# Quasar_Control_Board_v0_1.net
KiCad netlist of a schematic drawn in EAGLE
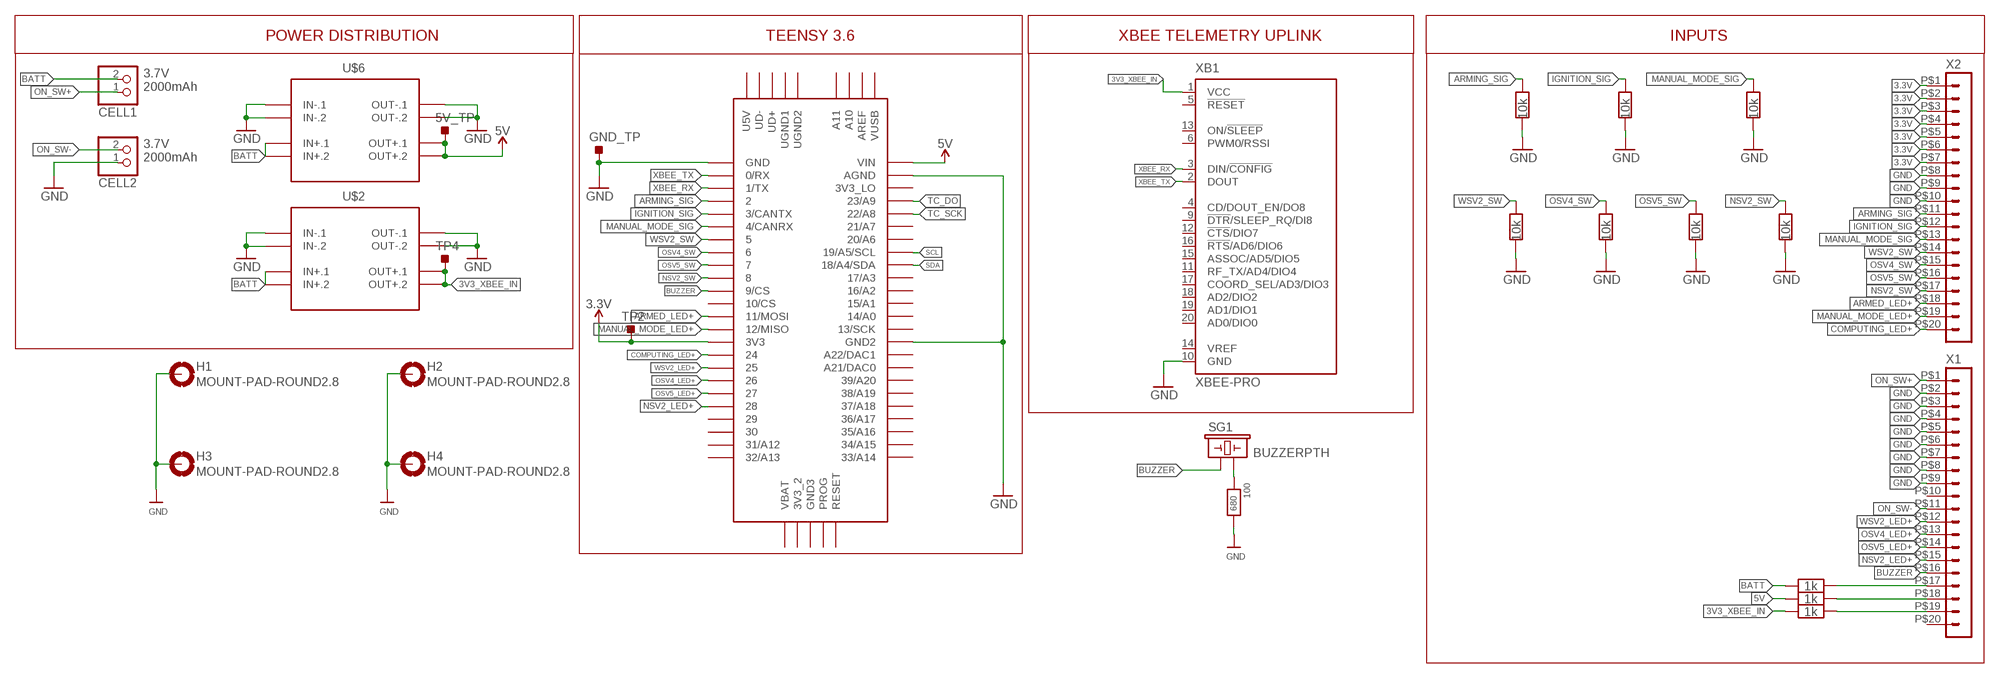
[diagram p0: schematic, sheet 1]

(export (version "E")
  (design (tool "Eeschema 10.0.6"))
  (components
    (comp (ref "5V_TP")
      (value "TESTPOINT_TPS-SMD-10SN")
      (footprint "eagle-import:TESTPOINT_SMD-10SN")
      (libsource (lib "eagle-import") (part "TESTPOINT_TPS-SMD-10SN"))
    )
    (comp (ref "100")
      (value "680")
      (footprint "eagle-import:0603")
      (libsource (lib "eagle-import") (part "RESISTOR0603"))
    )
    (comp (ref "CELL1")
      (value "JSTPH")
      (footprint "eagle-import:JSTPH2")
      (libsource (lib "eagle-import") (part "JST_2PIN"))
    )
    (comp (ref "CELL2")
      (value "JSTPH")
      (footprint "eagle-import:JSTPH2")
      (libsource (lib "eagle-import") (part "JST_2PIN"))
    )
    (comp (ref "GND_TP")
      (value "TESTPOINT_TPS-SMD-10SN")
      (footprint "eagle-import:TESTPOINT_SMD-10SN")
      (libsource (lib "eagle-import") (part "TESTPOINT_TPS-SMD-10SN"))
    )
    (comp (ref "H1")
      (value "MOUNT-PAD-ROUND2.8")
      (footprint "eagle-import:2,8-PAD")
      (libsource (lib "eagle-import") (part "MOUNT-PAD-ROUND2.8"))
    )
    (comp (ref "H2")
      (value "MOUNT-PAD-ROUND2.8")
      (footprint "eagle-import:2,8-PAD")
      (libsource (lib "eagle-import") (part "MOUNT-PAD-ROUND2.8"))
    )
    (comp (ref "H3")
      (value "MOUNT-PAD-ROUND2.8")
      (footprint "eagle-import:2,8-PAD")
      (libsource (lib "eagle-import") (part "MOUNT-PAD-ROUND2.8"))
    )
    (comp (ref "H4")
      (value "MOUNT-PAD-ROUND2.8")
      (footprint "eagle-import:2,8-PAD")
      (libsource (lib "eagle-import") (part "MOUNT-PAD-ROUND2.8"))
    )
    (comp (ref "R1")
      (value "10k")
      (footprint "eagle-import:0805")
      (libsource (lib "eagle-import") (part "RESISTOR0805"))
    )
    (comp (ref "R2")
      (value "10k")
      (footprint "eagle-import:0805")
      (libsource (lib "eagle-import") (part "RESISTOR0805"))
    )
    (comp (ref "R3")
      (value "10k")
      (footprint "eagle-import:0805")
      (libsource (lib "eagle-import") (part "RESISTOR0805"))
    )
    (comp (ref "R4")
      (value "10k")
      (footprint "eagle-import:0805")
      (libsource (lib "eagle-import") (part "RESISTOR0805"))
    )
    (comp (ref "R5")
      (value "10k")
      (footprint "eagle-import:0805")
      (libsource (lib "eagle-import") (part "RESISTOR0805"))
    )
    (comp (ref "R6")
      (value "10k")
      (footprint "eagle-import:0805")
      (libsource (lib "eagle-import") (part "RESISTOR0805"))
    )
    (comp (ref "R7")
      (value "10k")
      (footprint "eagle-import:0805")
      (libsource (lib "eagle-import") (part "RESISTOR0805"))
    )
    (comp (ref "R8")
      (value "1k")
      (footprint "eagle-import:0805")
      (libsource (lib "eagle-import") (part "RESISTOR0805"))
    )
    (comp (ref "R9")
      (value "1k")
      (footprint "eagle-import:0805")
      (libsource (lib "eagle-import") (part "RESISTOR0805"))
    )
    (comp (ref "R10")
      (value "1k")
      (footprint "eagle-import:0805")
      (libsource (lib "eagle-import") (part "RESISTOR0805"))
    )
    (comp (ref "SG1")
      (value "BUZZERPTH")
      (footprint "eagle-import:BUZZER-12MM")
      (libsource (lib "eagle-import") (part "BUZZERPTH"))
    )
    (comp (ref "TP2")
      (value "TESTPOINT_TPS-SMD-10SN")
      (footprint "eagle-import:TESTPOINT_SMD-10SN")
      (libsource (lib "eagle-import") (part "TESTPOINT_TPS-SMD-10SN"))
    )
    (comp (ref "TP4")
      (value "TESTPOINT_TPS-SMD-10SN")
      (footprint "eagle-import:TESTPOINT_SMD-10SN")
      (libsource (lib "eagle-import") (part "TESTPOINT_TPS-SMD-10SN"))
    )
    (comp (ref "U$1")
      (value "TEENSY_3.5/3.6")
      (footprint "eagle-import:TEENSY_3.5_3.6")
      (libsource (lib "eagle-import") (part "TEENSY_3.5/3.6"))
    )
    (comp (ref "U$2")
      (value "12V_LC_REG")
      (footprint "eagle-import:DC-DC-STEP-DOWN-MP1584")
      (libsource (lib "eagle-import") (part "DC-DC-STEP-DOWN-MP1584"))
    )
    (comp (ref "U$6")
      (value "12V_LC_REG")
      (footprint "eagle-import:DC-DC-STEP-DOWN-MP1584")
      (libsource (lib "eagle-import") (part "DC-DC-STEP-DOWN-MP1584"))
    )
    (comp (ref "X1")
      (value "HEADER_POS20_44914-2001")
      (footprint "eagle-import:44914-2001")
      (libsource (lib "eagle-import") (part "HEADER_POS20_?44914-2001"))
    )
    (comp (ref "X2")
      (value "HEADER_POS20_44914-2001")
      (footprint "eagle-import:44914-2001")
      (libsource (lib "eagle-import") (part "HEADER_POS20_?44914-2001"))
    )
    (comp (ref "XB1")
      (value "XBEE-PRO")
      (footprint "eagle-import:XBEE-PRO")
      (fields (field (name "MPN") "XBP24-AWI-001"))
      (libsource (lib "eagle-import") (part "XBEE-PRO"))
    )
  )
  (nets
    (net (code "1") (name "3.3V") (class "Default")
      (node (ref "TP2") (pin "TP") (pinfunction "TP_TP") (pintype "passive"))
      (node (ref "U$1") (pin "3V3") (pinfunction "3V3_3V3") (pintype "bidirectional"))
      (node (ref "X2") (pin "P$1") (pinfunction "1_P$1") (pintype "passive"))
      (node (ref "X2") (pin "P$2") (pinfunction "2_P$2") (pintype "passive"))
      (node (ref "X2") (pin "P$3") (pinfunction "3_P$3") (pintype "passive"))
      (node (ref "X2") (pin "P$4") (pinfunction "4_P$4") (pintype "passive"))
      (node (ref "X2") (pin "P$5") (pinfunction "5_P$5") (pintype "passive"))
      (node (ref "X2") (pin "P$6") (pinfunction "6_P$6") (pintype "passive"))
      (node (ref "X2") (pin "P$7") (pinfunction "7_P$7") (pintype "passive"))
    )
    (net (code "2") (name "3V3_XBEE_IN") (class "Default")
      (node (ref "R10") (pin "2") (pinfunction "2_2") (pintype "passive"))
      (node (ref "TP4") (pin "TP") (pinfunction "TP_TP") (pintype "passive"))
      (node (ref "U$2") (pin "OUT+.1") (pinfunction "OUT+.1_OUT+.1") (pintype "bidirectional"))
      (node (ref "U$2") (pin "OUT+.2") (pinfunction "OUT+.2_OUT+.2") (pintype "bidirectional"))
      (node (ref "XB1") (pin "1") (pinfunction "VCC_1") (pintype "power_in"))
    )
    (net (code "3") (name "5V") (class "Default")
      (node (ref "5V_TP") (pin "TP") (pinfunction "TP_TP") (pintype "passive"))
      (node (ref "R9") (pin "2") (pinfunction "2_2") (pintype "passive"))
      (node (ref "U$1") (pin "VIN") (pinfunction "VIN_VIN") (pintype "bidirectional"))
      (node (ref "U$6") (pin "OUT+.1") (pinfunction "OUT+.1_OUT+.1") (pintype "bidirectional"))
      (node (ref "U$6") (pin "OUT+.2") (pinfunction "OUT+.2_OUT+.2") (pintype "bidirectional"))
    )
    (net (code "4") (name "ARMED_LED+") (class "Default")
      (node (ref "U$1") (pin "11/MOSI") (pinfunction "11/MOSI_11/MOSI") (pintype "bidirectional"))
      (node (ref "X2") (pin "P$18") (pinfunction "18_P$18") (pintype "passive"))
    )
    (net (code "5") (name "ARMING_SIG") (class "Default")
      (node (ref "R1") (pin "1") (pinfunction "1_1") (pintype "passive"))
      (node (ref "U$1") (pin "2") (pinfunction "2_2") (pintype "bidirectional"))
      (node (ref "X2") (pin "P$11") (pinfunction "11_P$11") (pintype "passive"))
    )
    (net (code "6") (name "BATT") (class "Default")
      (node (ref "CELL1") (pin "2") (pinfunction "2_2") (pintype "passive"))
      (node (ref "R8") (pin "2") (pinfunction "2_2") (pintype "passive"))
      (node (ref "U$2") (pin "IN+.1") (pinfunction "IN+.1_IN+.1") (pintype "bidirectional"))
      (node (ref "U$2") (pin "IN+.2") (pinfunction "IN+.2_IN+.2") (pintype "bidirectional"))
      (node (ref "U$6") (pin "IN+.1") (pinfunction "IN+.1_IN+.1") (pintype "bidirectional"))
      (node (ref "U$6") (pin "IN+.2") (pinfunction "IN+.2_IN+.2") (pintype "bidirectional"))
    )
    (net (code "7") (name "BUZZER") (class "Default")
      (node (ref "SG1") (pin "+") (pinfunction "1_+") (pintype "passive"))
      (node (ref "U$1") (pin "9/CS") (pinfunction "9/CS_9/CS") (pintype "bidirectional"))
      (node (ref "X1") (pin "P$16") (pinfunction "16_P$16") (pintype "passive"))
    )
    (net (code "8") (name "COMPUTING_LED+") (class "Default")
      (node (ref "U$1") (pin "24") (pinfunction "24_24") (pintype "bidirectional"))
      (node (ref "X2") (pin "P$20") (pinfunction "20_P$20") (pintype "passive"))
    )
    (net (code "9") (name "GND") (class "Default")
      (node (ref "100") (pin "2") (pinfunction "2_2") (pintype "passive"))
      (node (ref "CELL2") (pin "1") (pinfunction "1_1") (pintype "passive"))
      (node (ref "GND_TP") (pin "TP") (pinfunction "TP_TP") (pintype "passive"))
      (node (ref "H1") (pin "B2,8") (pinfunction "MOUNT_B2,8") (pintype "passive"))
      (node (ref "H2") (pin "B2,8") (pinfunction "MOUNT_B2,8") (pintype "passive"))
      (node (ref "H3") (pin "B2,8") (pinfunction "MOUNT_B2,8") (pintype "passive"))
      (node (ref "H4") (pin "B2,8") (pinfunction "MOUNT_B2,8") (pintype "passive"))
      (node (ref "R1") (pin "2") (pinfunction "2_2") (pintype "passive"))
      (node (ref "R2") (pin "2") (pinfunction "2_2") (pintype "passive"))
      (node (ref "R3") (pin "2") (pinfunction "2_2") (pintype "passive"))
      (node (ref "R4") (pin "2") (pinfunction "2_2") (pintype "passive"))
      (node (ref "R5") (pin "2") (pinfunction "2_2") (pintype "passive"))
      (node (ref "R6") (pin "2") (pinfunction "2_2") (pintype "passive"))
      (node (ref "R7") (pin "2") (pinfunction "2_2") (pintype "passive"))
      (node (ref "U$1") (pin "AGND") (pinfunction "AGND_AGND") (pintype "bidirectional"))
      (node (ref "U$1") (pin "GND") (pinfunction "GND_GND") (pintype "bidirectional"))
      (node (ref "U$1") (pin "GND2") (pinfunction "GND2_GND2") (pintype "bidirectional"))
      (node (ref "U$2") (pin "IN-.1") (pinfunction "IN-.1_IN-.1") (pintype "bidirectional"))
      (node (ref "U$2") (pin "IN-.2") (pinfunction "IN-.2_IN-.2") (pintype "bidirectional"))
      (node (ref "U$2") (pin "OUT-.1") (pinfunction "OUT-.1_OUT-.1") (pintype "bidirectional"))
      (node (ref "U$2") (pin "OUT-.2") (pinfunction "OUT-.2_OUT-.2") (pintype "bidirectional"))
      (node (ref "U$6") (pin "IN-.1") (pinfunction "IN-.1_IN-.1") (pintype "bidirectional"))
      (node (ref "U$6") (pin "IN-.2") (pinfunction "IN-.2_IN-.2") (pintype "bidirectional"))
      (node (ref "U$6") (pin "OUT-.1") (pinfunction "OUT-.1_OUT-.1") (pintype "bidirectional"))
      (node (ref "U$6") (pin "OUT-.2") (pinfunction "OUT-.2_OUT-.2") (pintype "bidirectional"))
      (node (ref "X1") (pin "P$2") (pinfunction "2_P$2") (pintype "passive"))
      (node (ref "X1") (pin "P$3") (pinfunction "3_P$3") (pintype "passive"))
      (node (ref "X1") (pin "P$4") (pinfunction "4_P$4") (pintype "passive"))
      (node (ref "X1") (pin "P$5") (pinfunction "5_P$5") (pintype "passive"))
      (node (ref "X1") (pin "P$6") (pinfunction "6_P$6") (pintype "passive"))
      (node (ref "X1") (pin "P$7") (pinfunction "7_P$7") (pintype "passive"))
      (node (ref "X1") (pin "P$8") (pinfunction "8_P$8") (pintype "passive"))
      (node (ref "X1") (pin "P$9") (pinfunction "9_P$9") (pintype "passive"))
      (node (ref "X2") (pin "P$10") (pinfunction "10_P$10") (pintype "passive"))
      (node (ref "X2") (pin "P$8") (pinfunction "8_P$8") (pintype "passive"))
      (node (ref "X2") (pin "P$9") (pinfunction "9_P$9") (pintype "passive"))
      (node (ref "XB1") (pin "10") (pinfunction "GND_10") (pintype "power_in"))
    )
    (net (code "10") (name "IGNITION_SIG") (class "Default")
      (node (ref "R2") (pin "1") (pinfunction "1_1") (pintype "passive"))
      (node (ref "U$1") (pin "3/CANTX") (pinfunction "3/CANTX_3/CANTX") (pintype "bidirectional"))
      (node (ref "X2") (pin "P$12") (pinfunction "12_P$12") (pintype "passive"))
    )
    (net (code "11") (name "MANUAL_MODE_LED+") (class "Default")
      (node (ref "U$1") (pin "12/MISO") (pinfunction "12/MISO_12/MISO") (pintype "bidirectional"))
      (node (ref "X2") (pin "P$19") (pinfunction "19_P$19") (pintype "passive"))
    )
    (net (code "12") (name "MANUAL_MODE_SIG") (class "Default")
      (node (ref "R3") (pin "1") (pinfunction "1_1") (pintype "passive"))
      (node (ref "U$1") (pin "4/CANRX") (pinfunction "4/CANRX_4/CANRX") (pintype "bidirectional"))
      (node (ref "X2") (pin "P$13") (pinfunction "13_P$13") (pintype "passive"))
    )
    (net (code "13") (name "NSV2_LED+") (class "Default")
      (node (ref "U$1") (pin "28") (pinfunction "28_28") (pintype "bidirectional"))
      (node (ref "X1") (pin "P$15") (pinfunction "15_P$15") (pintype "passive"))
    )
    (net (code "14") (name "NSV2_SW") (class "Default")
      (node (ref "R7") (pin "1") (pinfunction "1_1") (pintype "passive"))
      (node (ref "U$1") (pin "8") (pinfunction "8_8") (pintype "bidirectional"))
      (node (ref "X2") (pin "P$17") (pinfunction "17_P$17") (pintype "passive"))
    )
    (net (code "15") (name "Net-(SG1-2)") (class "Default")
      (node (ref "100") (pin "1") (pinfunction "1_1") (pintype "passive"))
      (node (ref "SG1") (pin "-") (pinfunction "2_-") (pintype "passive"))
    )
    (net (code "16") (name "Net-(X1-17)") (class "Default")
      (node (ref "R8") (pin "1") (pinfunction "1_1") (pintype "passive"))
      (node (ref "X1") (pin "P$17") (pinfunction "17_P$17") (pintype "passive"))
    )
    (net (code "17") (name "Net-(X1-18)") (class "Default")
      (node (ref "R9") (pin "1") (pinfunction "1_1") (pintype "passive"))
      (node (ref "X1") (pin "P$18") (pinfunction "18_P$18") (pintype "passive"))
    )
    (net (code "18") (name "Net-(X1-19)") (class "Default")
      (node (ref "R10") (pin "1") (pinfunction "1_1") (pintype "passive"))
      (node (ref "X1") (pin "P$19") (pinfunction "19_P$19") (pintype "passive"))
    )
    (net (code "19") (name "ON_SW+") (class "Default")
      (node (ref "CELL1") (pin "1") (pinfunction "1_1") (pintype "passive"))
      (node (ref "X1") (pin "P$1") (pinfunction "1_P$1") (pintype "passive"))
    )
    (net (code "20") (name "ON_SW-") (class "Default")
      (node (ref "CELL2") (pin "2") (pinfunction "2_2") (pintype "passive"))
      (node (ref "X1") (pin "P$11") (pinfunction "11_P$11") (pintype "passive"))
    )
    (net (code "21") (name "OSV4_LED+") (class "Default")
      (node (ref "U$1") (pin "26") (pinfunction "26_26") (pintype "bidirectional"))
      (node (ref "X1") (pin "P$13") (pinfunction "13_P$13") (pintype "passive"))
    )
    (net (code "22") (name "OSV4_SW") (class "Default")
      (node (ref "R5") (pin "1") (pinfunction "1_1") (pintype "passive"))
      (node (ref "U$1") (pin "6") (pinfunction "6_6") (pintype "bidirectional"))
      (node (ref "X2") (pin "P$15") (pinfunction "15_P$15") (pintype "passive"))
    )
    (net (code "23") (name "OSV5_LED+") (class "Default")
      (node (ref "U$1") (pin "27") (pinfunction "27_27") (pintype "bidirectional"))
      (node (ref "X1") (pin "P$14") (pinfunction "14_P$14") (pintype "passive"))
    )
    (net (code "24") (name "OSV5_SW") (class "Default")
      (node (ref "R6") (pin "1") (pinfunction "1_1") (pintype "passive"))
      (node (ref "U$1") (pin "7") (pinfunction "7_7") (pintype "bidirectional"))
      (node (ref "X2") (pin "P$16") (pinfunction "16_P$16") (pintype "passive"))
    )
    (net (code "25") (name "SCL") (class "Default")
      (node (ref "U$1") (pin "19/A5/SCL") (pinfunction "19/A5/SCL_19/A5/SCL") (pintype "bidirectional"))
    )
    (net (code "26") (name "SDA") (class "Default")
      (node (ref "U$1") (pin "18/A4/SDA") (pinfunction "18/A4/SDA_18/A4/SDA") (pintype "bidirectional"))
    )
    (net (code "27") (name "TC_DO") (class "Default")
      (node (ref "U$1") (pin "23/A9") (pinfunction "23/A9_23/A9") (pintype "bidirectional"))
    )
    (net (code "28") (name "TC_SCK") (class "Default")
      (node (ref "U$1") (pin "22/A8") (pinfunction "22/A8_22/A8") (pintype "bidirectional"))
    )
    (net (code "29") (name "WSV2_LED+") (class "Default")
      (node (ref "U$1") (pin "25") (pinfunction "25_25") (pintype "bidirectional"))
      (node (ref "X1") (pin "P$12") (pinfunction "12_P$12") (pintype "passive"))
    )
    (net (code "30") (name "WSV2_SW") (class "Default")
      (node (ref "R4") (pin "1") (pinfunction "1_1") (pintype "passive"))
      (node (ref "U$1") (pin "5") (pinfunction "5_5") (pintype "bidirectional"))
      (node (ref "X2") (pin "P$14") (pinfunction "14_P$14") (pintype "passive"))
    )
    (net (code "31") (name "XBEE_RX") (class "Default")
      (node (ref "U$1") (pin "1/TX") (pinfunction "1/TX_1/TX") (pintype "bidirectional"))
      (node (ref "XB1") (pin "3") (pinfunction "DIN/~{CONFIG}_3") (pintype "input"))
    )
    (net (code "32") (name "XBEE_TX") (class "Default")
      (node (ref "U$1") (pin "0/RX") (pinfunction "0/RX_0/RX") (pintype "bidirectional"))
      (node (ref "XB1") (pin "2") (pinfunction "DOUT_2") (pintype "output"))
    )
    (net (code "33") (name "unconnected-(U$1-A21{slash}DAC0-Pad21{slash}DAC0)") (class "Default")
      (node (ref "U$1") (pin "21/DAC0") (pinfunction "A21/DAC0_21/DAC0") (pintype "bidirectional"))
    )
    (net (code "34") (name "unconnected-(U$1-Pad3V3_2)") (class "Default")
      (node (ref "U$1") (pin "3V3_2") (pinfunction "3V3_2_3V3_2") (pintype "bidirectional"))
    )
    (net (code "35") (name "unconnected-(U$1-Pad3V3_LO)") (class "Default")
      (node (ref "U$1") (pin "3V3_LO") (pinfunction "3V3_LO_3V3_LO") (pintype "bidirectional"))
    )
    (net (code "36") (name "unconnected-(U$1-Pad10{slash}CS)") (class "Default")
      (node (ref "U$1") (pin "10/CS") (pinfunction "10/CS_10/CS") (pintype "bidirectional"))
    )
    (net (code "37") (name "unconnected-(U$1-Pad13{slash}SCK)") (class "Default")
      (node (ref "U$1") (pin "13/SCK") (pinfunction "13/SCK_13/SCK") (pintype "bidirectional"))
    )
    (net (code "38") (name "unconnected-(U$1-Pad14{slash}A0)") (class "Default")
      (node (ref "U$1") (pin "14/A0") (pinfunction "14/A0_14/A0") (pintype "bidirectional"))
    )
    (net (code "39") (name "unconnected-(U$1-Pad15{slash}A1)") (class "Default")
      (node (ref "U$1") (pin "15/A1") (pinfunction "15/A1_15/A1") (pintype "bidirectional"))
    )
    (net (code "40") (name "unconnected-(U$1-Pad16{slash}A2)") (class "Default")
      (node (ref "U$1") (pin "16/A2") (pinfunction "16/A2_16/A2") (pintype "bidirectional"))
    )
    (net (code "41") (name "unconnected-(U$1-Pad17{slash}A3)") (class "Default")
      (node (ref "U$1") (pin "17/A3") (pinfunction "17/A3_17/A3") (pintype "bidirectional"))
    )
    (net (code "42") (name "unconnected-(U$1-Pad20{slash}A6)") (class "Default")
      (node (ref "U$1") (pin "20/A6") (pinfunction "20/A6_20/A6") (pintype "bidirectional"))
    )
    (net (code "43") (name "unconnected-(U$1-Pad21{slash}A7)") (class "Default")
      (node (ref "U$1") (pin "21/A7") (pinfunction "21/A7_21/A7") (pintype "bidirectional"))
    )
    (net (code "44") (name "unconnected-(U$1-Pad29)") (class "Default")
      (node (ref "U$1") (pin "29") (pinfunction "29_29") (pintype "bidirectional"))
    )
    (net (code "45") (name "unconnected-(U$1-Pad30)") (class "Default")
      (node (ref "U$1") (pin "30") (pinfunction "30_30") (pintype "bidirectional"))
    )
    (net (code "46") (name "unconnected-(U$1-Pad31{slash}A12)") (class "Default")
      (node (ref "U$1") (pin "31/A12") (pinfunction "31/A12_31/A12") (pintype "bidirectional"))
    )
    (net (code "47") (name "unconnected-(U$1-Pad32{slash}A13)") (class "Default")
      (node (ref "U$1") (pin "32/A13") (pinfunction "32/A13_32/A13") (pintype "bidirectional"))
    )
    (net (code "48") (name "unconnected-(U$1-Pad33{slash}A14)") (class "Default")
      (node (ref "U$1") (pin "33/A14") (pinfunction "33/A14_33/A14") (pintype "bidirectional"))
    )
    (net (code "49") (name "unconnected-(U$1-Pad34{slash}A15)") (class "Default")
      (node (ref "U$1") (pin "34/A15") (pinfunction "34/A15_34/A15") (pintype "bidirectional"))
    )
    (net (code "50") (name "unconnected-(U$1-Pad35{slash}A16)") (class "Default")
      (node (ref "U$1") (pin "35/A16") (pinfunction "35/A16_35/A16") (pintype "bidirectional"))
    )
    (net (code "51") (name "unconnected-(U$1-Pad36{slash}A17)") (class "Default")
      (node (ref "U$1") (pin "36/A17") (pinfunction "36/A17_36/A17") (pintype "bidirectional"))
    )
    (net (code "52") (name "unconnected-(U$1-Pad37{slash}A18)") (class "Default")
      (node (ref "U$1") (pin "37/A18") (pinfunction "37/A18_37/A18") (pintype "bidirectional"))
    )
    (net (code "53") (name "unconnected-(U$1-Pad38{slash}A19)") (class "Default")
      (node (ref "U$1") (pin "38/A19") (pinfunction "38/A19_38/A19") (pintype "bidirectional"))
    )
    (net (code "54") (name "unconnected-(U$1-Pad39{slash}A20)") (class "Default")
      (node (ref "U$1") (pin "39/A20") (pinfunction "39/A20_39/A20") (pintype "bidirectional"))
    )
    (net (code "55") (name "unconnected-(U$1-PadA10)") (class "Default")
      (node (ref "U$1") (pin "A10") (pinfunction "A10_A10") (pintype "bidirectional"))
    )
    (net (code "56") (name "unconnected-(U$1-PadA11)") (class "Default")
      (node (ref "U$1") (pin "A11") (pinfunction "A11_A11") (pintype "bidirectional"))
    )
    (net (code "57") (name "unconnected-(U$1-PadA22{slash}DAC1)") (class "Default")
      (node (ref "U$1") (pin "A22/DAC1") (pinfunction "A22/DAC1_A22/DAC1") (pintype "bidirectional"))
    )
    (net (code "58") (name "unconnected-(U$1-PadAREF)") (class "Default")
      (node (ref "U$1") (pin "AREF") (pinfunction "AREF_AREF") (pintype "bidirectional"))
    )
    (net (code "59") (name "unconnected-(U$1-PadGND3)") (class "Default")
      (node (ref "U$1") (pin "GND3") (pinfunction "GND3_GND3") (pintype "bidirectional"))
    )
    (net (code "60") (name "unconnected-(U$1-PadPROG)") (class "Default")
      (node (ref "U$1") (pin "PROG") (pinfunction "PROG_PROG") (pintype "bidirectional"))
    )
    (net (code "61") (name "unconnected-(U$1-PadRESET)") (class "Default")
      (node (ref "U$1") (pin "RESET") (pinfunction "RESET_RESET") (pintype "bidirectional"))
    )
    (net (code "62") (name "unconnected-(U$1-PadU5V)") (class "Default")
      (node (ref "U$1") (pin "U5V") (pinfunction "U5V_U5V") (pintype "bidirectional"))
    )
    (net (code "63") (name "unconnected-(U$1-PadUD+)") (class "Default")
      (node (ref "U$1") (pin "UD+") (pinfunction "UD+_UD+") (pintype "bidirectional"))
    )
    (net (code "64") (name "unconnected-(U$1-PadUD-)") (class "Default")
      (node (ref "U$1") (pin "UD-") (pinfunction "UD-_UD-") (pintype "bidirectional"))
    )
    (net (code "65") (name "unconnected-(U$1-PadUGND1)") (class "Default")
      (node (ref "U$1") (pin "UGND1") (pinfunction "UGND1_UGND1") (pintype "bidirectional"))
    )
    (net (code "66") (name "unconnected-(U$1-PadUGND2)") (class "Default")
      (node (ref "U$1") (pin "UGND2") (pinfunction "UGND2_UGND2") (pintype "bidirectional"))
    )
    (net (code "67") (name "unconnected-(U$1-PadVBAT)") (class "Default")
      (node (ref "U$1") (pin "VBAT") (pinfunction "VBAT_VBAT") (pintype "bidirectional"))
    )
    (net (code "68") (name "unconnected-(U$1-PadVUSB)") (class "Default")
      (node (ref "U$1") (pin "VUSB") (pinfunction "VUSB_VUSB") (pintype "bidirectional"))
    )
    (net (code "69") (name "unconnected-(X1-10-PadP$10)") (class "Default")
      (node (ref "X1") (pin "P$10") (pinfunction "10_P$10") (pintype "passive"))
    )
    (net (code "70") (name "unconnected-(X1-20-PadP$20)") (class "Default")
      (node (ref "X1") (pin "P$20") (pinfunction "20_P$20") (pintype "passive"))
    )
    (net (code "71") (name "unconnected-(XB1-AD0{slash}DIO0-Pad20)") (class "Default")
      (node (ref "XB1") (pin "20") (pinfunction "AD0/DIO0_20") (pintype "bidirectional"))
    )
    (net (code "72") (name "unconnected-(XB1-AD1{slash}DIO1-Pad19)") (class "Default")
      (node (ref "XB1") (pin "19") (pinfunction "AD1/DIO1_19") (pintype "bidirectional"))
    )
    (net (code "73") (name "unconnected-(XB1-AD2{slash}DIO2-Pad18)") (class "Default")
      (node (ref "XB1") (pin "18") (pinfunction "AD2/DIO2_18") (pintype "bidirectional"))
    )
    (net (code "74") (name "unconnected-(XB1-ASSOC{slash}AD5{slash}DIO5-Pad15)") (class "Default")
      (node (ref "XB1") (pin "15") (pinfunction "ASSOC/AD5/DIO5_15") (pintype "bidirectional"))
    )
    (net (code "75") (name "unconnected-(XB1-CD{slash}DOUT_EN{slash}DO8-Pad4)") (class "Default")
      (node (ref "XB1") (pin "4") (pinfunction "CD/DOUT_EN/DO8_4") (pintype "output"))
    )
    (net (code "76") (name "unconnected-(XB1-COORD_SEL{slash}AD3{slash}DIO3-Pad17)") (class "Default")
      (node (ref "XB1") (pin "17") (pinfunction "COORD_SEL/AD3/DIO3_17") (pintype "bidirectional"))
    )
    (net (code "77") (name "unconnected-(XB1-ON{slash}~{SLEEP}-Pad13)") (class "Default")
      (node (ref "XB1") (pin "13") (pinfunction "ON/~{SLEEP}_13") (pintype "output"))
    )
    (net (code "78") (name "unconnected-(XB1-PWM0{slash}RSSI-Pad6)") (class "Default")
      (node (ref "XB1") (pin "6") (pinfunction "PWM0/RSSI_6") (pintype "output"))
    )
    (net (code "79") (name "unconnected-(XB1-RF_TX{slash}AD4{slash}DIO4-Pad11)") (class "Default")
      (node (ref "XB1") (pin "11") (pinfunction "RF_TX/AD4/DIO4_11") (pintype "bidirectional"))
    )
    (net (code "80") (name "unconnected-(XB1-VREF-Pad14)") (class "Default")
      (node (ref "XB1") (pin "14") (pinfunction "VREF_14") (pintype "input"))
    )
    (net (code "81") (name "unconnected-(XB1-~{CTS}{slash}DIO7-Pad12)") (class "Default")
      (node (ref "XB1") (pin "12") (pinfunction "~{CTS}/DIO7_12") (pintype "bidirectional"))
    )
    (net (code "82") (name "unconnected-(XB1-~{DTR}{slash}SLEEP_RQ{slash}DI8-Pad9)") (class "Default")
      (node (ref "XB1") (pin "9") (pinfunction "~{DTR}/SLEEP_RQ/DI8_9") (pintype "bidirectional"))
    )
    (net (code "83") (name "unconnected-(XB1-~{RESET}-Pad5)") (class "Default")
      (node (ref "XB1") (pin "5") (pinfunction "~{RESET}_5") (pintype "input"))
    )
    (net (code "84") (name "unconnected-(XB1-~{RTS}{slash}AD6{slash}DIO6-Pad16)") (class "Default")
      (node (ref "XB1") (pin "16") (pinfunction "~{RTS}/AD6/DIO6_16") (pintype "bidirectional"))
    )
  )
)
